# Water_Schematic2_1.net
KiCad netlist of a schematic drawn in EAGLE
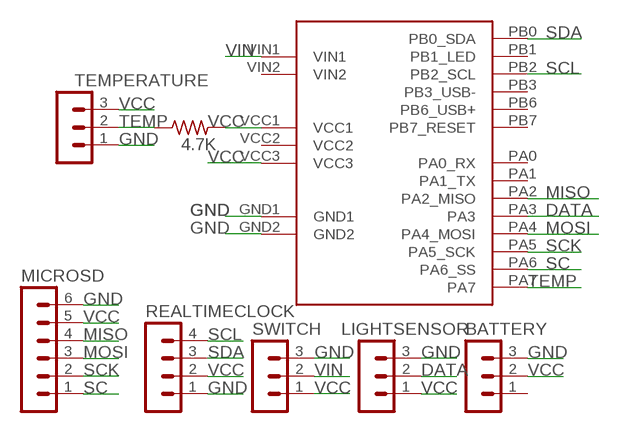
[diagram p0: schematic, sheet 1]

(export (version "E")
  (design (tool "Eeschema 10.0.6"))
  (components
    (comp (ref "BATTERY")
      (value "MA03-1")
      (footprint "eagle-import:MA03-1")
      (libsource (lib "eagle-import") (part "MA03-1"))
    )
    (comp (ref "LIGHTSENSOR")
      (value "MA03-1")
      (footprint "eagle-import:MA03-1")
      (libsource (lib "eagle-import") (part "MA03-1"))
    )
    (comp (ref "MICROSD")
      (value "MA06-1")
      (footprint "eagle-import:MA06-1")
      (libsource (lib "eagle-import") (part "MA06-1"))
    )
    (comp (ref "R1")
      (value "4.7K")
      (footprint "eagle-import:0204_7")
      (libsource (lib "eagle-import") (part "R-US_0204/7"))
    )
    (comp (ref "REALTIMECLOCK")
      (value "MA04-1")
      (footprint "eagle-import:MA04-1")
      (libsource (lib "eagle-import") (part "MA04-1"))
    )
    (comp (ref "SWITCH")
      (value "MA03-1")
      (footprint "eagle-import:MA03-1")
      (libsource (lib "eagle-import") (part "MA03-1"))
    )
    (comp (ref "TEMPERATURE")
      (value "MA03-1")
      (footprint "eagle-import:MA03-1")
      (libsource (lib "eagle-import") (part "MA03-1"))
    )
    (comp (ref "U$1")
      (value "DIGISPARK_PRO")
      (footprint "eagle-import:DIGISPARK_PRO")
      (libsource (lib "eagle-import") (part "DIGISPARK_PRO"))
    )
  )
  (nets
    (net (code "1") (name "/DATA") (class "Default")
      (node (ref "LIGHTSENSOR") (pin "2") (pinfunction "2_2") (pintype "passive"))
      (node (ref "U$1") (pin "PA3") (pinfunction "PA3_PA3") (pintype "bidirectional"))
    )
    (net (code "2") (name "/GND") (class "Default")
      (node (ref "BATTERY") (pin "3") (pinfunction "3_3") (pintype "passive"))
      (node (ref "LIGHTSENSOR") (pin "3") (pinfunction "3_3") (pintype "passive"))
      (node (ref "MICROSD") (pin "6") (pinfunction "6_6") (pintype "passive"))
      (node (ref "REALTIMECLOCK") (pin "1") (pinfunction "1_1") (pintype "passive"))
      (node (ref "SWITCH") (pin "3") (pinfunction "3_3") (pintype "passive"))
      (node (ref "TEMPERATURE") (pin "1") (pinfunction "1_1") (pintype "passive"))
      (node (ref "U$1") (pin "GND1") (pinfunction "GND1_GND1") (pintype "bidirectional"))
      (node (ref "U$1") (pin "GND2") (pinfunction "GND2_GND2") (pintype "bidirectional"))
    )
    (net (code "3") (name "/MISO") (class "Default")
      (node (ref "MICROSD") (pin "4") (pinfunction "4_4") (pintype "passive"))
      (node (ref "U$1") (pin "PA2") (pinfunction "PA2_MISO_PA2") (pintype "bidirectional"))
    )
    (net (code "4") (name "/MOSI") (class "Default")
      (node (ref "MICROSD") (pin "3") (pinfunction "3_3") (pintype "passive"))
      (node (ref "U$1") (pin "PA4") (pinfunction "PA4_MOSI_PA4") (pintype "bidirectional"))
    )
    (net (code "5") (name "/SC") (class "Default")
      (node (ref "MICROSD") (pin "1") (pinfunction "1_1") (pintype "passive"))
      (node (ref "U$1") (pin "PA6") (pinfunction "PA6_SS_PA6") (pintype "bidirectional"))
    )
    (net (code "6") (name "/SCK") (class "Default")
      (node (ref "MICROSD") (pin "2") (pinfunction "2_2") (pintype "passive"))
      (node (ref "U$1") (pin "PA5") (pinfunction "PA5_SCK_PA5") (pintype "bidirectional"))
    )
    (net (code "7") (name "/SCL") (class "Default")
      (node (ref "REALTIMECLOCK") (pin "4") (pinfunction "4_4") (pintype "passive"))
      (node (ref "U$1") (pin "PB2") (pinfunction "PB2_SCL_PB2") (pintype "bidirectional"))
    )
    (net (code "8") (name "/SDA") (class "Default")
      (node (ref "REALTIMECLOCK") (pin "3") (pinfunction "3_3") (pintype "passive"))
      (node (ref "U$1") (pin "PB0") (pinfunction "PB0_SDA_PB0") (pintype "bidirectional"))
    )
    (net (code "9") (name "/TEMP") (class "Default")
      (node (ref "R1") (pin "1") (pinfunction "1_1") (pintype "passive"))
      (node (ref "TEMPERATURE") (pin "2") (pinfunction "2_2") (pintype "passive"))
      (node (ref "U$1") (pin "PA7") (pinfunction "PA7_PA7") (pintype "bidirectional"))
    )
    (net (code "10") (name "/VCC") (class "Default")
      (node (ref "BATTERY") (pin "2") (pinfunction "2_2") (pintype "passive"))
      (node (ref "LIGHTSENSOR") (pin "1") (pinfunction "1_1") (pintype "passive"))
      (node (ref "MICROSD") (pin "5") (pinfunction "5_5") (pintype "passive"))
      (node (ref "R1") (pin "2") (pinfunction "2_2") (pintype "passive"))
      (node (ref "REALTIMECLOCK") (pin "2") (pinfunction "2_2") (pintype "passive"))
      (node (ref "SWITCH") (pin "1") (pinfunction "1_1") (pintype "passive"))
      (node (ref "TEMPERATURE") (pin "3") (pinfunction "3_3") (pintype "passive"))
      (node (ref "U$1") (pin "VCC1") (pinfunction "VCC1_VCC1") (pintype "bidirectional"))
      (node (ref "U$1") (pin "VCC3") (pinfunction "VCC3_VCC3") (pintype "bidirectional"))
    )
    (net (code "11") (name "/VIN") (class "Default")
      (node (ref "SWITCH") (pin "2") (pinfunction "2_2") (pintype "passive"))
      (node (ref "U$1") (pin "VIN1") (pinfunction "VIN1_VIN1") (pintype "bidirectional"))
    )
    (net (code "12") (name "unconnected-(BATTERY-Pad1)") (class "Default")
      (node (ref "BATTERY") (pin "1") (pinfunction "1_1") (pintype "passive"))
    )
    (net (code "13") (name "unconnected-(U$1-PA0_RX-PadPA0)") (class "Default")
      (node (ref "U$1") (pin "PA0") (pinfunction "PA0_RX_PA0") (pintype "bidirectional"))
    )
    (net (code "14") (name "unconnected-(U$1-PA1_TX-PadPA1)") (class "Default")
      (node (ref "U$1") (pin "PA1") (pinfunction "PA1_TX_PA1") (pintype "bidirectional"))
    )
    (net (code "15") (name "unconnected-(U$1-PB1_LED-PadPB1)") (class "Default")
      (node (ref "U$1") (pin "PB1") (pinfunction "PB1_LED_PB1") (pintype "bidirectional"))
    )
    (net (code "16") (name "unconnected-(U$1-PB3_USB--PadPB3)") (class "Default")
      (node (ref "U$1") (pin "PB3") (pinfunction "PB3_USB-_PB3") (pintype "bidirectional"))
    )
    (net (code "17") (name "unconnected-(U$1-PB6_USB+-PadPB6)") (class "Default")
      (node (ref "U$1") (pin "PB6") (pinfunction "PB6_USB+_PB6") (pintype "bidirectional"))
    )
    (net (code "18") (name "unconnected-(U$1-PB7_RESET-PadPB7)") (class "Default")
      (node (ref "U$1") (pin "PB7") (pinfunction "PB7_RESET_PB7") (pintype "bidirectional"))
    )
    (net (code "19") (name "unconnected-(U$1-PadVCC2)") (class "Default")
      (node (ref "U$1") (pin "VCC2") (pinfunction "VCC2_VCC2") (pintype "bidirectional"))
    )
    (net (code "20") (name "unconnected-(U$1-PadVIN2)") (class "Default")
      (node (ref "U$1") (pin "VIN2") (pinfunction "VIN2_VIN2") (pintype "bidirectional"))
    )
  )
)
